# trigger.net
KiCad netlist of a schematic drawn in EAGLE
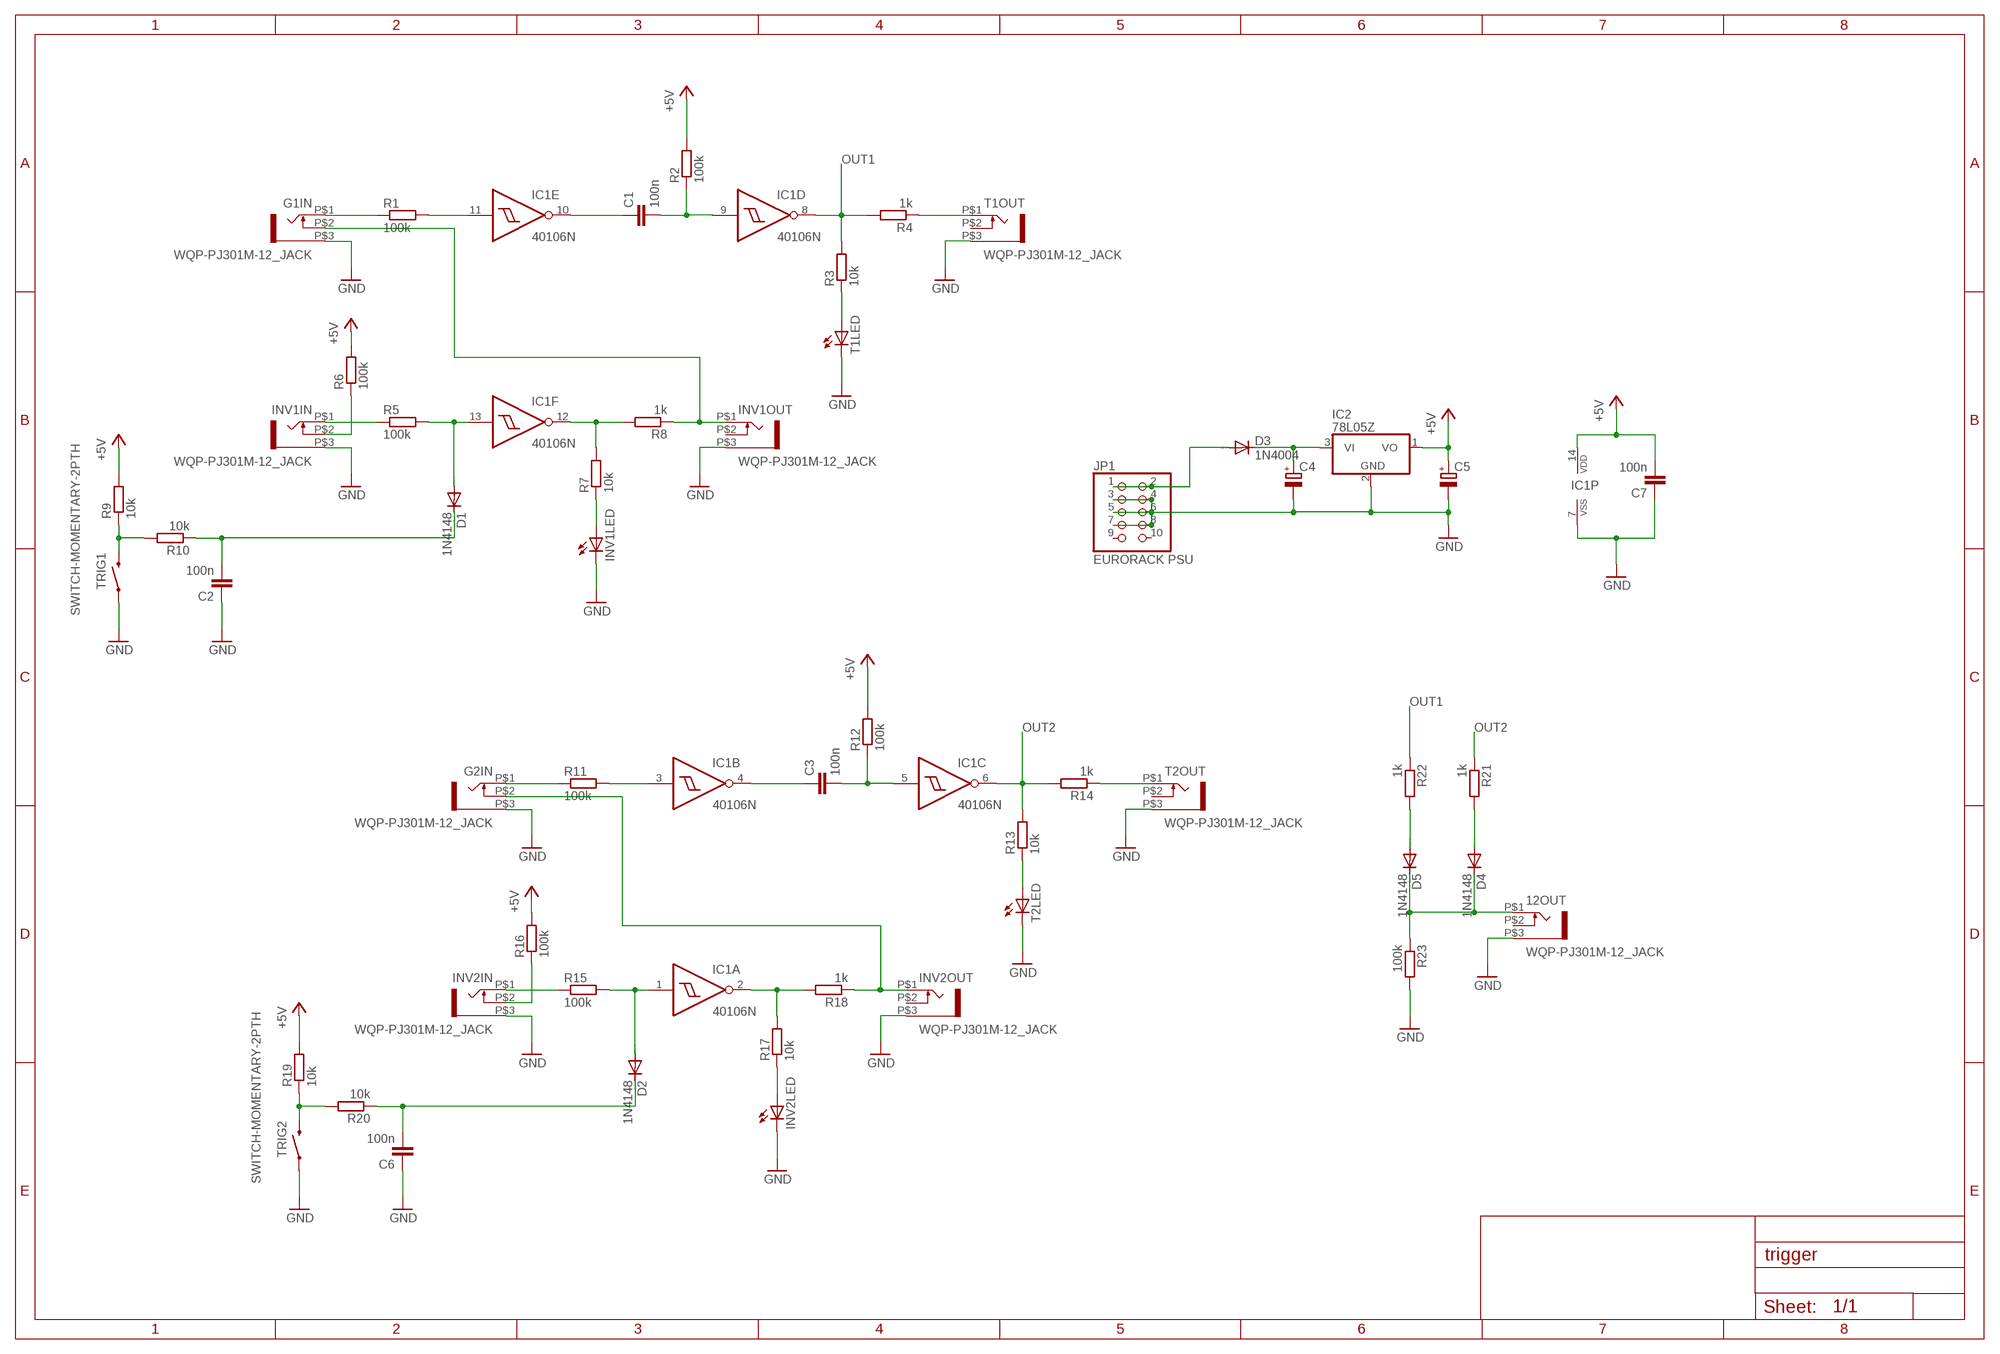
[diagram p0: schematic, sheet 1]

(export (version "E")
  (design (tool "Eeschema 10.0.6"))
  (components
    (comp (ref "12OUT")
      (value "WQP-PJ301M-12_JACK")
      (footprint "eagle-import:WQP-PJ301M-12_JACK")
      (libsource (lib "eagle-import") (part "WQP-PJ301M-12_JACK"))
    )
    (comp (ref "C1")
      (value "100n")
      (footprint "eagle-import:C025-025X050")
      (libsource (lib "eagle-import") (part "C-EU025-025X050"))
    )
    (comp (ref "C2")
      (value "100n")
      (footprint "eagle-import:C025-025X050")
      (libsource (lib "eagle-import") (part "C-EU025-025X050"))
    )
    (comp (ref "C3")
      (value "100n")
      (footprint "eagle-import:C025-025X050")
      (libsource (lib "eagle-import") (part "C-EU025-025X050"))
    )
    (comp (ref "C4")
      (value "CPOL-EUE2.5-5")
      (footprint "eagle-import:E2,5-5")
      (libsource (lib "eagle-import") (part "CPOL-EUE2.5-5"))
    )
    (comp (ref "C5")
      (value "CPOL-EUE2.5-5")
      (footprint "eagle-import:E2,5-5")
      (libsource (lib "eagle-import") (part "CPOL-EUE2.5-5"))
    )
    (comp (ref "C6")
      (value "100n")
      (footprint "eagle-import:C025-025X050")
      (libsource (lib "eagle-import") (part "C-EU025-025X050"))
    )
    (comp (ref "C7")
      (value "100n")
      (footprint "eagle-import:C025-025X050")
      (libsource (lib "eagle-import") (part "C-EU025-025X050"))
    )
    (comp (ref "D1")
      (value "1N4148")
      (footprint "eagle-import:D-2.5")
      (libsource (lib "eagle-import") (part "DIODE-D-2.5"))
    )
    (comp (ref "D2")
      (value "1N4148")
      (footprint "eagle-import:D-2.5")
      (libsource (lib "eagle-import") (part "DIODE-D-2.5"))
    )
    (comp (ref "D3")
      (value "1N4004")
      (footprint "eagle-import:D-2.5")
      (libsource (lib "eagle-import") (part "DIODE-D-2.5"))
    )
    (comp (ref "D4")
      (value "1N4148")
      (footprint "eagle-import:D-2.5")
      (libsource (lib "eagle-import") (part "DIODE-D-2.5"))
    )
    (comp (ref "D5")
      (value "1N4148")
      (footprint "eagle-import:D-2.5")
      (libsource (lib "eagle-import") (part "DIODE-D-2.5"))
    )
    (comp (ref "G1IN")
      (value "WQP-PJ301M-12_JACK")
      (footprint "eagle-import:WQP-PJ301M-12_JACK")
      (libsource (lib "eagle-import") (part "WQP-PJ301M-12_JACK"))
    )
    (comp (ref "G2IN")
      (value "WQP-PJ301M-12_JACK")
      (footprint "eagle-import:WQP-PJ301M-12_JACK")
      (libsource (lib "eagle-import") (part "WQP-PJ301M-12_JACK"))
    )
    (comp (ref "IC1")
      (value "40106N")
      (footprint "eagle-import:DIL14")
      (libsource (lib "eagle-import") (part "40106N"))
    )
    (comp (ref "IC2")
      (value "78L05Z")
      (footprint "eagle-import:TO92")
      (libsource (lib "eagle-import") (part "78ZL05"))
    )
    (comp (ref "INV1IN")
      (value "WQP-PJ301M-12_JACK")
      (footprint "eagle-import:WQP-PJ301M-12_JACK")
      (libsource (lib "eagle-import") (part "WQP-PJ301M-12_JACK"))
    )
    (comp (ref "INV1LED")
      (value "LED3MM")
      (footprint "eagle-import:LED3MM")
      (libsource (lib "eagle-import") (part "LED3MM"))
    )
    (comp (ref "INV1OUT")
      (value "WQP-PJ301M-12_JACK")
      (footprint "eagle-import:WQP-PJ301M-12_JACK")
      (libsource (lib "eagle-import") (part "WQP-PJ301M-12_JACK"))
    )
    (comp (ref "INV2IN")
      (value "WQP-PJ301M-12_JACK")
      (footprint "eagle-import:WQP-PJ301M-12_JACK")
      (libsource (lib "eagle-import") (part "WQP-PJ301M-12_JACK"))
    )
    (comp (ref "INV2LED")
      (value "LED3MM")
      (footprint "eagle-import:LED3MM")
      (libsource (lib "eagle-import") (part "LED3MM"))
    )
    (comp (ref "INV2OUT")
      (value "WQP-PJ301M-12_JACK")
      (footprint "eagle-import:WQP-PJ301M-12_JACK")
      (libsource (lib "eagle-import") (part "WQP-PJ301M-12_JACK"))
    )
    (comp (ref "JP1")
      (value "EURORACK PSU")
      (footprint "eagle-import:2X05")
      (libsource (lib "eagle-import") (part "PINHD-2X5"))
    )
    (comp (ref "R1")
      (value "100k")
      (footprint "eagle-import:0204V")
      (libsource (lib "eagle-import") (part "R-EU_0204/2V"))
    )
    (comp (ref "R2")
      (value "100k")
      (footprint "eagle-import:0204V")
      (libsource (lib "eagle-import") (part "R-EU_0204/2V"))
    )
    (comp (ref "R3")
      (value "10k")
      (footprint "eagle-import:0204V")
      (libsource (lib "eagle-import") (part "R-EU_0204/2V"))
    )
    (comp (ref "R4")
      (value "1k")
      (footprint "eagle-import:0204V")
      (libsource (lib "eagle-import") (part "R-EU_0204/2V"))
    )
    (comp (ref "R5")
      (value "100k")
      (footprint "eagle-import:0204V")
      (libsource (lib "eagle-import") (part "R-EU_0204/2V"))
    )
    (comp (ref "R6")
      (value "100k")
      (footprint "eagle-import:0204V")
      (libsource (lib "eagle-import") (part "R-EU_0204/2V"))
    )
    (comp (ref "R7")
      (value "10k")
      (footprint "eagle-import:0204V")
      (libsource (lib "eagle-import") (part "R-EU_0204/2V"))
    )
    (comp (ref "R8")
      (value "1k")
      (footprint "eagle-import:0204V")
      (libsource (lib "eagle-import") (part "R-EU_0204/2V"))
    )
    (comp (ref "R9")
      (value "10k")
      (footprint "eagle-import:0204V")
      (libsource (lib "eagle-import") (part "R-EU_0204/2V"))
    )
    (comp (ref "R10")
      (value "10k")
      (footprint "eagle-import:0204V")
      (libsource (lib "eagle-import") (part "R-EU_0204/2V"))
    )
    (comp (ref "R11")
      (value "100k")
      (footprint "eagle-import:0204V")
      (libsource (lib "eagle-import") (part "R-EU_0204/2V"))
    )
    (comp (ref "R12")
      (value "100k")
      (footprint "eagle-import:0204V")
      (libsource (lib "eagle-import") (part "R-EU_0204/2V"))
    )
    (comp (ref "R13")
      (value "10k")
      (footprint "eagle-import:0204V")
      (libsource (lib "eagle-import") (part "R-EU_0204/2V"))
    )
    (comp (ref "R14")
      (value "1k")
      (footprint "eagle-import:0204V")
      (libsource (lib "eagle-import") (part "R-EU_0204/2V"))
    )
    (comp (ref "R15")
      (value "100k")
      (footprint "eagle-import:0204V")
      (libsource (lib "eagle-import") (part "R-EU_0204/2V"))
    )
    (comp (ref "R16")
      (value "100k")
      (footprint "eagle-import:0204V")
      (libsource (lib "eagle-import") (part "R-EU_0204/2V"))
    )
    (comp (ref "R17")
      (value "10k")
      (footprint "eagle-import:0204V")
      (libsource (lib "eagle-import") (part "R-EU_0204/2V"))
    )
    (comp (ref "R18")
      (value "1k")
      (footprint "eagle-import:0204V")
      (libsource (lib "eagle-import") (part "R-EU_0204/2V"))
    )
    (comp (ref "R19")
      (value "10k")
      (footprint "eagle-import:0204V")
      (libsource (lib "eagle-import") (part "R-EU_0204/2V"))
    )
    (comp (ref "R20")
      (value "10k")
      (footprint "eagle-import:0204V")
      (libsource (lib "eagle-import") (part "R-EU_0204/2V"))
    )
    (comp (ref "R21")
      (value "1k")
      (footprint "eagle-import:0204V")
      (libsource (lib "eagle-import") (part "R-EU_0204/2V"))
    )
    (comp (ref "R22")
      (value "1k")
      (footprint "eagle-import:0204V")
      (libsource (lib "eagle-import") (part "R-EU_0204/2V"))
    )
    (comp (ref "R23")
      (value "100k")
      (footprint "eagle-import:0204V")
      (libsource (lib "eagle-import") (part "R-EU_0204/2V"))
    )
    (comp (ref "T1LED")
      (value "LED3MM")
      (footprint "eagle-import:LED3MM")
      (libsource (lib "eagle-import") (part "LED3MM"))
    )
    (comp (ref "T1OUT")
      (value "WQP-PJ301M-12_JACK")
      (footprint "eagle-import:WQP-PJ301M-12_JACK")
      (libsource (lib "eagle-import") (part "WQP-PJ301M-12_JACK"))
    )
    (comp (ref "T2LED")
      (value "LED3MM")
      (footprint "eagle-import:LED3MM")
      (libsource (lib "eagle-import") (part "LED3MM"))
    )
    (comp (ref "T2OUT")
      (value "WQP-PJ301M-12_JACK")
      (footprint "eagle-import:WQP-PJ301M-12_JACK")
      (libsource (lib "eagle-import") (part "WQP-PJ301M-12_JACK"))
    )
    (comp (ref "TRIG1")
      (value "SWITCH-MOMENTARY-2PTH")
      (footprint "eagle-import:TACTILE-PTH")
      (libsource (lib "eagle-import") (part "SWITCH-MOMENTARY-2PTH"))
    )
    (comp (ref "TRIG2")
      (value "SWITCH-MOMENTARY-2PTH")
      (footprint "eagle-import:TACTILE-PTH")
      (libsource (lib "eagle-import") (part "SWITCH-MOMENTARY-2PTH"))
    )
  )
  (nets
    (net (code "1") (name "+5V") (class "Default")
      (node (ref "C5") (pin "+") (pinfunction "+_+") (pintype "passive"))
      (node (ref "C7") (pin "2") (pinfunction "2_2") (pintype "passive"))
      (node (ref "IC1") (pin "14") (pinfunction "VDD_14") (pintype "power_in"))
      (node (ref "IC2") (pin "1") (pinfunction "VO_1") (pintype "passive"))
      (node (ref "R12") (pin "2") (pinfunction "2_2") (pintype "passive"))
      (node (ref "R16") (pin "2") (pinfunction "2_2") (pintype "passive"))
      (node (ref "R19") (pin "2") (pinfunction "2_2") (pintype "passive"))
      (node (ref "R2") (pin "2") (pinfunction "2_2") (pintype "passive"))
      (node (ref "R6") (pin "2") (pinfunction "2_2") (pintype "passive"))
      (node (ref "R9") (pin "2") (pinfunction "2_2") (pintype "passive"))
    )
    (net (code "2") (name "/OUT1") (class "Default")
      (node (ref "IC1") (pin "8") (pinfunction "O_8") (pintype "output"))
      (node (ref "R22") (pin "1") (pinfunction "1_1") (pintype "passive"))
      (node (ref "R3") (pin "2") (pinfunction "2_2") (pintype "passive"))
      (node (ref "R4") (pin "2") (pinfunction "2_2") (pintype "passive"))
    )
    (net (code "3") (name "/OUT2") (class "Default")
      (node (ref "IC1") (pin "6") (pinfunction "O_6") (pintype "output"))
      (node (ref "R13") (pin "2") (pinfunction "2_2") (pintype "passive"))
      (node (ref "R14") (pin "2") (pinfunction "2_2") (pintype "passive"))
      (node (ref "R21") (pin "1") (pinfunction "1_1") (pintype "passive"))
    )
    (net (code "4") (name "GND") (class "Default")
      (node (ref "12OUT") (pin "P$3") (pinfunction "1_P$3") (pintype "passive"))
      (node (ref "C2") (pin "1") (pinfunction "1_1") (pintype "passive"))
      (node (ref "C4") (pin "-") (pinfunction "-_-") (pintype "passive"))
      (node (ref "C5") (pin "-") (pinfunction "-_-") (pintype "passive"))
      (node (ref "C6") (pin "1") (pinfunction "1_1") (pintype "passive"))
      (node (ref "C7") (pin "1") (pinfunction "1_1") (pintype "passive"))
      (node (ref "G1IN") (pin "P$3") (pinfunction "1_P$3") (pintype "passive"))
      (node (ref "G2IN") (pin "P$3") (pinfunction "1_P$3") (pintype "passive"))
      (node (ref "IC1") (pin "7") (pinfunction "VSS_7") (pintype "power_in"))
      (node (ref "IC2") (pin "2") (pinfunction "GND_2") (pintype "passive"))
      (node (ref "INV1IN") (pin "P$3") (pinfunction "1_P$3") (pintype "passive"))
      (node (ref "INV1LED") (pin "K") (pinfunction "C_K") (pintype "passive"))
      (node (ref "INV1OUT") (pin "P$3") (pinfunction "1_P$3") (pintype "passive"))
      (node (ref "INV2IN") (pin "P$3") (pinfunction "1_P$3") (pintype "passive"))
      (node (ref "INV2LED") (pin "K") (pinfunction "C_K") (pintype "passive"))
      (node (ref "INV2OUT") (pin "P$3") (pinfunction "1_P$3") (pintype "passive"))
      (node (ref "JP1") (pin "3") (pinfunction "3_3") (pintype "passive"))
      (node (ref "JP1") (pin "4") (pinfunction "4_4") (pintype "passive"))
      (node (ref "JP1") (pin "5") (pinfunction "5_5") (pintype "passive"))
      (node (ref "JP1") (pin "6") (pinfunction "6_6") (pintype "passive"))
      (node (ref "JP1") (pin "7") (pinfunction "7_7") (pintype "passive"))
      (node (ref "JP1") (pin "8") (pinfunction "8_8") (pintype "passive"))
      (node (ref "R23") (pin "2") (pinfunction "2_2") (pintype "passive"))
      (node (ref "T1LED") (pin "K") (pinfunction "C_K") (pintype "passive"))
      (node (ref "T1OUT") (pin "P$3") (pinfunction "1_P$3") (pintype "passive"))
      (node (ref "T2LED") (pin "K") (pinfunction "C_K") (pintype "passive"))
      (node (ref "T2OUT") (pin "P$3") (pinfunction "1_P$3") (pintype "passive"))
      (node (ref "TRIG1") (pin "1") (pinfunction "1_1") (pintype "passive"))
      (node (ref "TRIG2") (pin "1") (pinfunction "1_1") (pintype "passive"))
    )
    (net (code "5") (name "Net-(12OUT-2)") (class "Default")
      (node (ref "12OUT") (pin "P$1") (pinfunction "2_P$1") (pintype "passive"))
      (node (ref "D4") (pin "C") (pinfunction "C_C") (pintype "passive"))
      (node (ref "D5") (pin "C") (pinfunction "C_C") (pintype "passive"))
      (node (ref "R23") (pin "1") (pinfunction "1_1") (pintype "passive"))
    )
    (net (code "6") (name "Net-(C2-Pad2)") (class "Default")
      (node (ref "C2") (pin "2") (pinfunction "2_2") (pintype "passive"))
      (node (ref "D1") (pin "C") (pinfunction "C_C") (pintype "passive"))
      (node (ref "R10") (pin "1") (pinfunction "1_1") (pintype "passive"))
    )
    (net (code "7") (name "Net-(C6-Pad2)") (class "Default")
      (node (ref "C6") (pin "2") (pinfunction "2_2") (pintype "passive"))
      (node (ref "D2") (pin "C") (pinfunction "C_C") (pintype "passive"))
      (node (ref "R20") (pin "1") (pinfunction "1_1") (pintype "passive"))
    )
    (net (code "8") (name "Net-(D3-PadA)") (class "Default")
      (node (ref "D3") (pin "A") (pinfunction "A_A") (pintype "passive"))
      (node (ref "JP1") (pin "1") (pinfunction "1_1") (pintype "passive"))
      (node (ref "JP1") (pin "2") (pinfunction "2_2") (pintype "passive"))
    )
    (net (code "9") (name "Net-(D4-PadA)") (class "Default")
      (node (ref "D4") (pin "A") (pinfunction "A_A") (pintype "passive"))
      (node (ref "R21") (pin "2") (pinfunction "2_2") (pintype "passive"))
    )
    (net (code "10") (name "Net-(D5-PadA)") (class "Default")
      (node (ref "D5") (pin "A") (pinfunction "A_A") (pintype "passive"))
      (node (ref "R22") (pin "2") (pinfunction "2_2") (pintype "passive"))
    )
    (net (code "11") (name "Net-(G1IN-2)") (class "Default")
      (node (ref "G1IN") (pin "P$1") (pinfunction "2_P$1") (pintype "passive"))
      (node (ref "R1") (pin "1") (pinfunction "1_1") (pintype "passive"))
    )
    (net (code "12") (name "Net-(G1IN-3)") (class "Default")
      (node (ref "G1IN") (pin "P$2") (pinfunction "3_P$2") (pintype "passive"))
      (node (ref "INV1OUT") (pin "P$1") (pinfunction "2_P$1") (pintype "passive"))
      (node (ref "R8") (pin "1") (pinfunction "1_1") (pintype "passive"))
    )
    (net (code "13") (name "Net-(G2IN-2)") (class "Default")
      (node (ref "G2IN") (pin "P$1") (pinfunction "2_P$1") (pintype "passive"))
      (node (ref "R11") (pin "1") (pinfunction "1_1") (pintype "passive"))
    )
    (net (code "14") (name "Net-(G2IN-3)") (class "Default")
      (node (ref "G2IN") (pin "P$2") (pinfunction "3_P$2") (pintype "passive"))
      (node (ref "INV2OUT") (pin "P$1") (pinfunction "2_P$1") (pintype "passive"))
      (node (ref "R18") (pin "1") (pinfunction "1_1") (pintype "passive"))
    )
    (net (code "15") (name "Net-(IC1A-I)") (class "Default")
      (node (ref "D2") (pin "A") (pinfunction "A_A") (pintype "passive"))
      (node (ref "IC1") (pin "1") (pinfunction "I_1") (pintype "input"))
      (node (ref "R15") (pin "2") (pinfunction "2_2") (pintype "passive"))
    )
    (net (code "16") (name "Net-(IC1A-O)") (class "Default")
      (node (ref "IC1") (pin "2") (pinfunction "O_2") (pintype "output"))
      (node (ref "R17") (pin "2") (pinfunction "2_2") (pintype "passive"))
      (node (ref "R18") (pin "2") (pinfunction "2_2") (pintype "passive"))
    )
    (net (code "17") (name "Net-(IC1B-I)") (class "Default")
      (node (ref "IC1") (pin "3") (pinfunction "I_3") (pintype "input"))
      (node (ref "R11") (pin "2") (pinfunction "2_2") (pintype "passive"))
    )
    (net (code "18") (name "Net-(IC1B-O)") (class "Default")
      (node (ref "C3") (pin "1") (pinfunction "1_1") (pintype "passive"))
      (node (ref "IC1") (pin "4") (pinfunction "O_4") (pintype "output"))
    )
    (net (code "19") (name "Net-(IC1C-I)") (class "Default")
      (node (ref "C3") (pin "2") (pinfunction "2_2") (pintype "passive"))
      (node (ref "IC1") (pin "5") (pinfunction "I_5") (pintype "input"))
      (node (ref "R12") (pin "1") (pinfunction "1_1") (pintype "passive"))
    )
    (net (code "20") (name "Net-(IC1D-I)") (class "Default")
      (node (ref "C1") (pin "2") (pinfunction "2_2") (pintype "passive"))
      (node (ref "IC1") (pin "9") (pinfunction "I_9") (pintype "input"))
      (node (ref "R2") (pin "1") (pinfunction "1_1") (pintype "passive"))
    )
    (net (code "21") (name "Net-(IC1E-I)") (class "Default")
      (node (ref "IC1") (pin "11") (pinfunction "I_11") (pintype "input"))
      (node (ref "R1") (pin "2") (pinfunction "2_2") (pintype "passive"))
    )
    (net (code "22") (name "Net-(IC1E-O)") (class "Default")
      (node (ref "C1") (pin "1") (pinfunction "1_1") (pintype "passive"))
      (node (ref "IC1") (pin "10") (pinfunction "O_10") (pintype "output"))
    )
    (net (code "23") (name "Net-(IC1F-I)") (class "Default")
      (node (ref "D1") (pin "A") (pinfunction "A_A") (pintype "passive"))
      (node (ref "IC1") (pin "13") (pinfunction "I_13") (pintype "input"))
      (node (ref "R5") (pin "2") (pinfunction "2_2") (pintype "passive"))
    )
    (net (code "24") (name "Net-(IC1F-O)") (class "Default")
      (node (ref "IC1") (pin "12") (pinfunction "O_12") (pintype "output"))
      (node (ref "R7") (pin "2") (pinfunction "2_2") (pintype "passive"))
      (node (ref "R8") (pin "2") (pinfunction "2_2") (pintype "passive"))
    )
    (net (code "25") (name "Net-(IC2-VI)") (class "Default")
      (node (ref "C4") (pin "+") (pinfunction "+_+") (pintype "passive"))
      (node (ref "D3") (pin "C") (pinfunction "C_C") (pintype "passive"))
      (node (ref "IC2") (pin "3") (pinfunction "VI_3") (pintype "input"))
    )
    (net (code "26") (name "Net-(INV1IN-2)") (class "Default")
      (node (ref "INV1IN") (pin "P$1") (pinfunction "2_P$1") (pintype "passive"))
      (node (ref "R5") (pin "1") (pinfunction "1_1") (pintype "passive"))
    )
    (net (code "27") (name "Net-(INV1IN-3)") (class "Default")
      (node (ref "INV1IN") (pin "P$2") (pinfunction "3_P$2") (pintype "passive"))
      (node (ref "R6") (pin "1") (pinfunction "1_1") (pintype "passive"))
    )
    (net (code "28") (name "Net-(INV1LED-PadA)") (class "Default")
      (node (ref "INV1LED") (pin "A") (pinfunction "A_A") (pintype "passive"))
      (node (ref "R7") (pin "1") (pinfunction "1_1") (pintype "passive"))
    )
    (net (code "29") (name "Net-(INV2IN-2)") (class "Default")
      (node (ref "INV2IN") (pin "P$1") (pinfunction "2_P$1") (pintype "passive"))
      (node (ref "R15") (pin "1") (pinfunction "1_1") (pintype "passive"))
    )
    (net (code "30") (name "Net-(INV2IN-3)") (class "Default")
      (node (ref "INV2IN") (pin "P$2") (pinfunction "3_P$2") (pintype "passive"))
      (node (ref "R16") (pin "1") (pinfunction "1_1") (pintype "passive"))
    )
    (net (code "31") (name "Net-(INV2LED-PadA)") (class "Default")
      (node (ref "INV2LED") (pin "A") (pinfunction "A_A") (pintype "passive"))
      (node (ref "R17") (pin "1") (pinfunction "1_1") (pintype "passive"))
    )
    (net (code "32") (name "Net-(R3-Pad1)") (class "Default")
      (node (ref "R3") (pin "1") (pinfunction "1_1") (pintype "passive"))
      (node (ref "T1LED") (pin "A") (pinfunction "A_A") (pintype "passive"))
    )
    (net (code "33") (name "Net-(R13-Pad1)") (class "Default")
      (node (ref "R13") (pin "1") (pinfunction "1_1") (pintype "passive"))
      (node (ref "T2LED") (pin "A") (pinfunction "A_A") (pintype "passive"))
    )
    (net (code "34") (name "Net-(T1OUT-2)") (class "Default")
      (node (ref "R4") (pin "1") (pinfunction "1_1") (pintype "passive"))
      (node (ref "T1OUT") (pin "P$1") (pinfunction "2_P$1") (pintype "passive"))
    )
    (net (code "35") (name "Net-(T2OUT-2)") (class "Default")
      (node (ref "R14") (pin "1") (pinfunction "1_1") (pintype "passive"))
      (node (ref "T2OUT") (pin "P$1") (pinfunction "2_P$1") (pintype "passive"))
    )
    (net (code "36") (name "Net-(TRIG1-2)") (class "Default")
      (node (ref "R10") (pin "2") (pinfunction "2_2") (pintype "passive"))
      (node (ref "R9") (pin "1") (pinfunction "1_1") (pintype "passive"))
      (node (ref "TRIG1") (pin "3") (pinfunction "2_3") (pintype "passive"))
    )
    (net (code "37") (name "Net-(TRIG2-2)") (class "Default")
      (node (ref "R19") (pin "1") (pinfunction "1_1") (pintype "passive"))
      (node (ref "R20") (pin "2") (pinfunction "2_2") (pintype "passive"))
      (node (ref "TRIG2") (pin "3") (pinfunction "2_3") (pintype "passive"))
    )
    (net (code "38") (name "unconnected-(12OUT-3-PadP$2)") (class "Default")
      (node (ref "12OUT") (pin "P$2") (pinfunction "3_P$2") (pintype "passive"))
    )
    (net (code "39") (name "unconnected-(INV1OUT-3-PadP$2)") (class "Default")
      (node (ref "INV1OUT") (pin "P$2") (pinfunction "3_P$2") (pintype "passive"))
    )
    (net (code "40") (name "unconnected-(INV2OUT-3-PadP$2)") (class "Default")
      (node (ref "INV2OUT") (pin "P$2") (pinfunction "3_P$2") (pintype "passive"))
    )
    (net (code "41") (name "unconnected-(JP1-Pad9)") (class "Default")
      (node (ref "JP1") (pin "9") (pinfunction "9_9") (pintype "passive"))
    )
    (net (code "42") (name "unconnected-(JP1-Pad10)") (class "Default")
      (node (ref "JP1") (pin "10") (pinfunction "10_10") (pintype "passive"))
    )
    (net (code "43") (name "unconnected-(T1OUT-3-PadP$2)") (class "Default")
      (node (ref "T1OUT") (pin "P$2") (pinfunction "3_P$2") (pintype "passive"))
    )
    (net (code "44") (name "unconnected-(T2OUT-3-PadP$2)") (class "Default")
      (node (ref "T2OUT") (pin "P$2") (pinfunction "3_P$2") (pintype "passive"))
    )
  )
)
